# ultrasonic_tx.net
KiCad netlist of a schematic drawn in Altium Designer
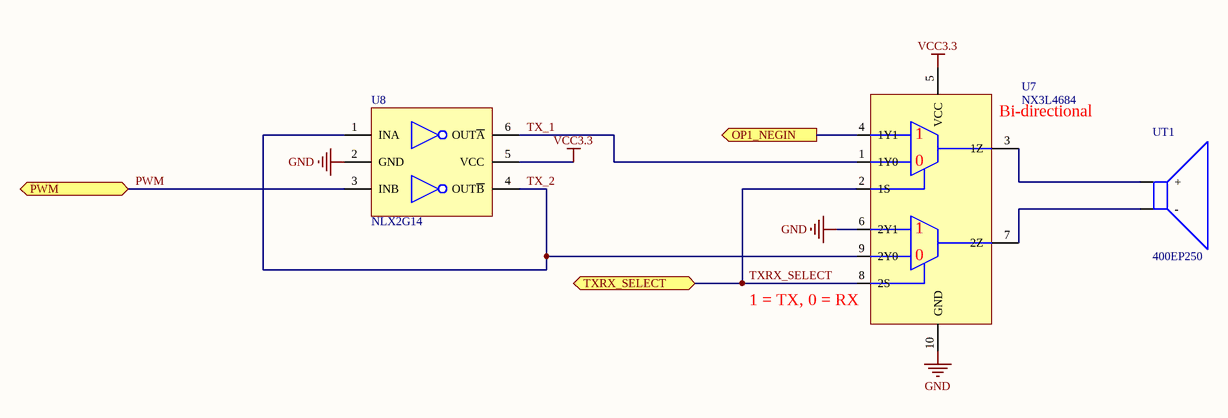
[diagram p0: ultrasonic_tx.SchDoc]

(export (version "E")
  (design (tool "Eeschema 10.0.6"))
  (components
    (comp (ref "U7")
      (value "NX3L4684")
      (footprint "QFN50P155X200X13-10N")
      (description "IC ANALOG SWITCH SPDT 10XQFN")
      (libsource (lib "opo_general") (part "NX3L4684"))
    )
    (comp (ref "U8")
      (value "NLX2G14")
      (footprint "ULLGA6")
      (description "IC INVERTER DUAL SCHMTRIG ULLGA6")
      (libsource (lib "opo_general") (part "NLX2G14"))
    )
    (comp (ref "UT1")
      (value "400EP250")
      (footprint "Transducer recepticle")
      (description "Air Ultrasounic Ceramic Transducers")
      (libsource (lib "opo_general") (part "Tranducer"))
    )
  )
  (nets
    (net (code "1") (name "/OP1_NEGIN") (class "Default")
      (node (ref "U7") (pin "4") (pinfunction "1Y1_4") (pintype "passive"))
    )
    (net (code "2") (name "/PWM") (class "Default")
      (node (ref "U8") (pin "3") (pinfunction "INB_3") (pintype "passive"))
    )
    (net (code "3") (name "/TXRX_SELECT") (class "Default")
      (node (ref "U7") (pin "2") (pinfunction "1S_2") (pintype "passive"))
      (node (ref "U7") (pin "8") (pinfunction "2S_8") (pintype "passive"))
    )
    (net (code "4") (name "/TX_1") (class "Default")
      (node (ref "U7") (pin "1") (pinfunction "1Y0_1") (pintype "passive"))
      (node (ref "U8") (pin "6") (pinfunction "OUT~{A}_6") (pintype "passive"))
    )
    (net (code "5") (name "/TX_2") (class "Default")
      (node (ref "U7") (pin "9") (pinfunction "2Y0_9") (pintype "passive"))
      (node (ref "U8") (pin "1") (pinfunction "INA_1") (pintype "passive"))
      (node (ref "U8") (pin "4") (pinfunction "OUT~{B}_4") (pintype "passive"))
    )
    (net (code "6") (name "GND") (class "Default")
      (node (ref "U7") (pin "10") (pinfunction "GND_10") (pintype "passive"))
      (node (ref "U7") (pin "6") (pinfunction "2Y1_6") (pintype "passive"))
      (node (ref "U8") (pin "2") (pinfunction "GND_2") (pintype "passive"))
    )
    (net (code "7") (name "Net-(U7-1Z)") (class "Default")
      (node (ref "U7") (pin "3") (pinfunction "1Z_3") (pintype "passive"))
      (node (ref "UT1") (pin "2") (pinfunction "+_2") (pintype "passive"))
    )
    (net (code "8") (name "Net-(U7-2Z)") (class "Default")
      (node (ref "U7") (pin "7") (pinfunction "2Z_7") (pintype "passive"))
      (node (ref "UT1") (pin "1") (pinfunction "-_1") (pintype "passive"))
    )
    (net (code "9") (name "VCC3.3") (class "Default")
      (node (ref "U7") (pin "5") (pinfunction "VCC_5") (pintype "passive"))
      (node (ref "U8") (pin "5") (pinfunction "VCC_5") (pintype "passive"))
    )
  )
)
